# LEDS1.net
KiCad netlist of a schematic drawn in Altium Designer
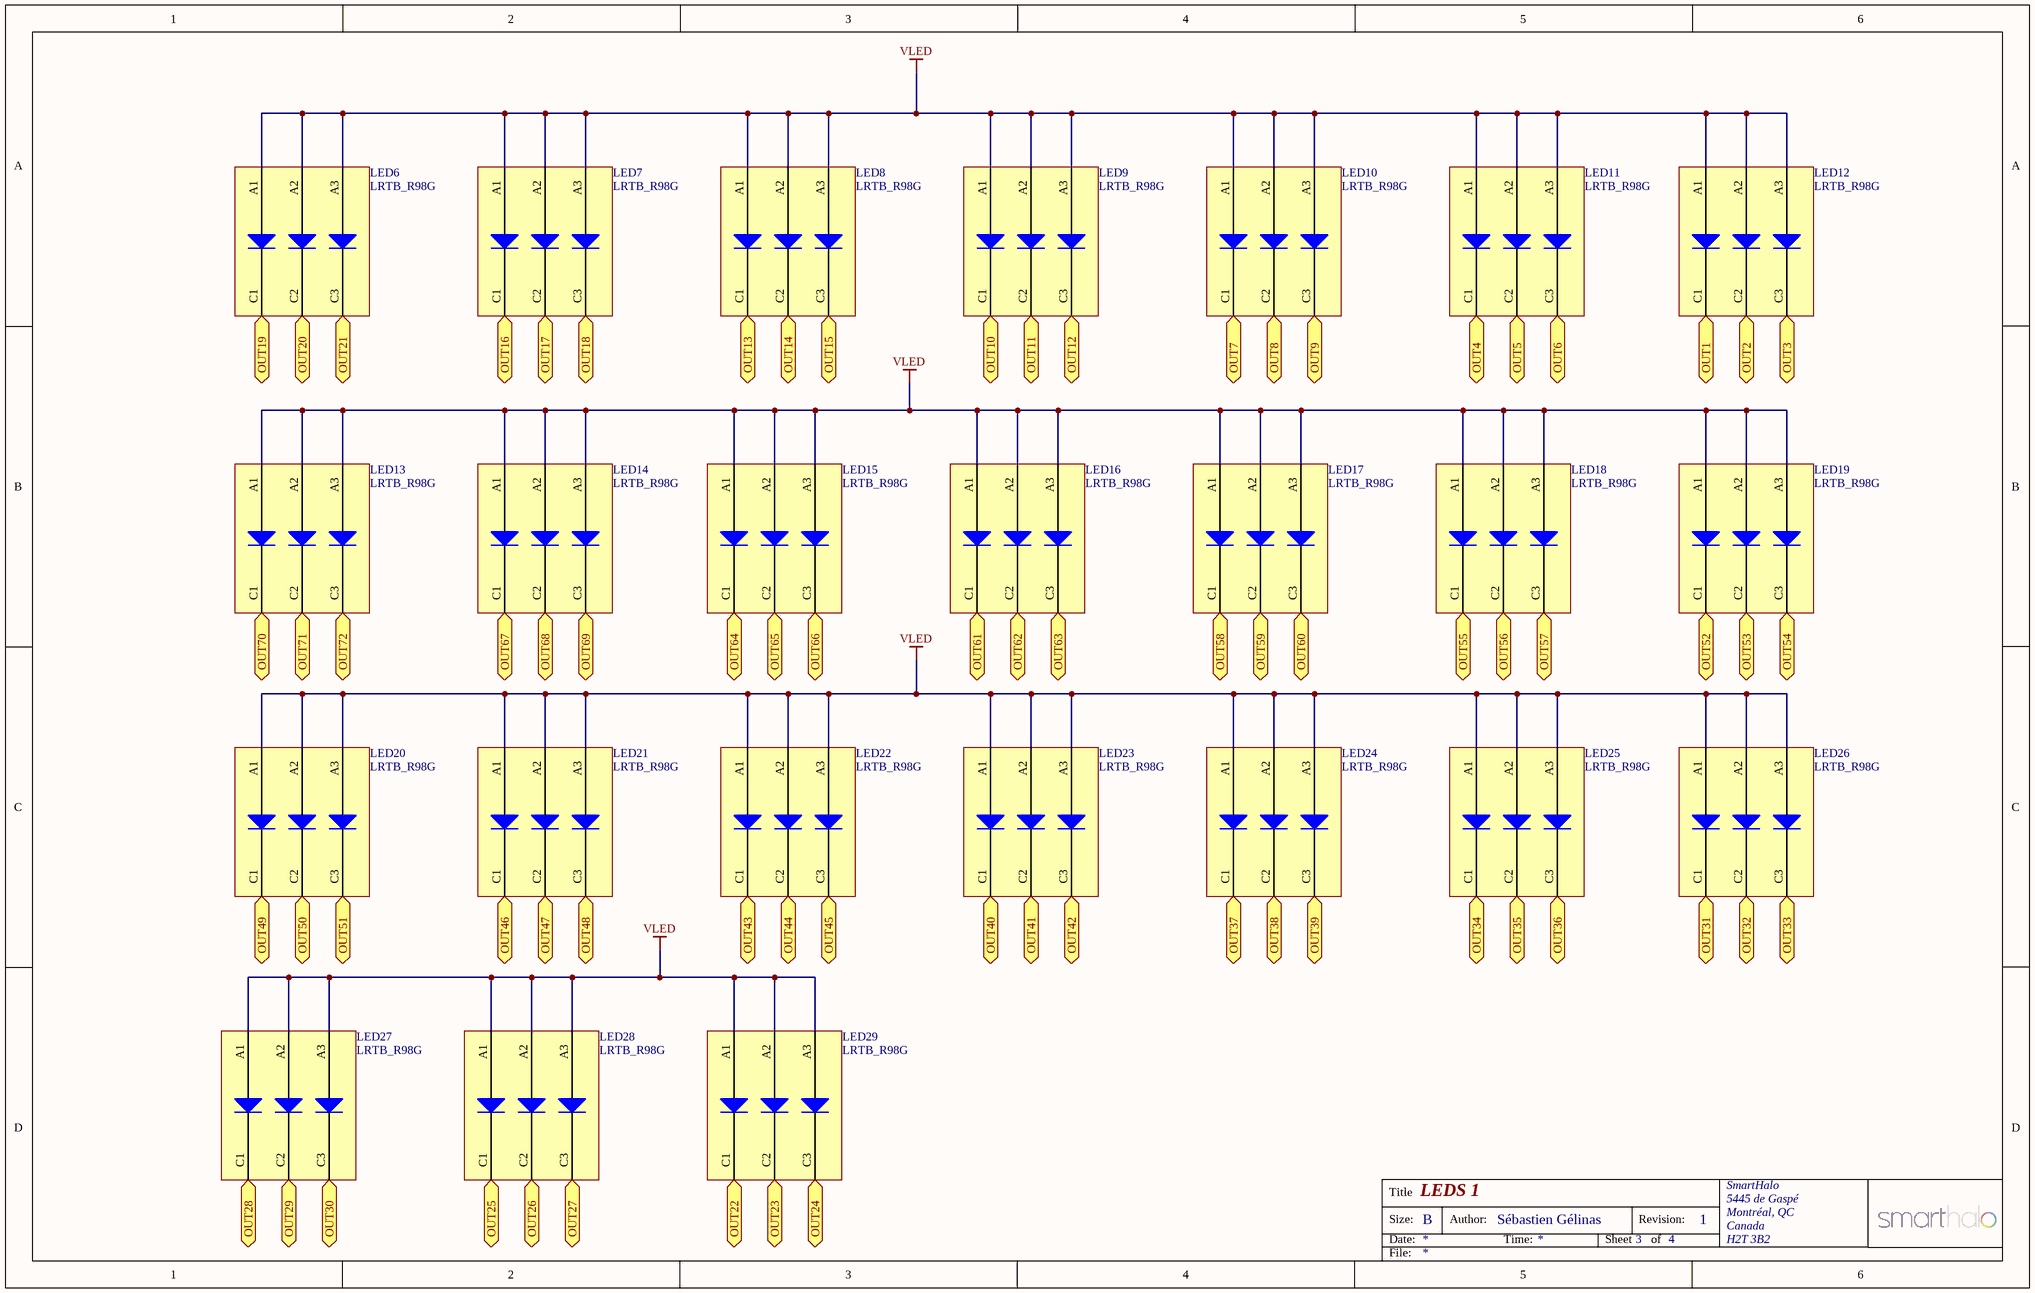
[diagram p0: LEDS1.SchDoc]

(export (version "E")
  (design (tool "Eeschema 10.0.6"))
  (components
    (comp (ref "LED6")
      (value "LRTB_R98G")
      (footprint "LRTB_R98G")
      (description "IC RGB LED OSRAM")
      (fields (field (name "MANUFACTURER") "OSRAM"))
      (libsource (lib "SmartHalo_Symbols") (part "LRTB_R98G"))
    )
    (comp (ref "LED7")
      (value "LRTB_R98G")
      (footprint "LRTB_R98G")
      (description "IC RGB LED OSRAM")
      (fields (field (name "MANUFACTURER") "OSRAM"))
      (libsource (lib "SmartHalo_Symbols") (part "LRTB_R98G"))
    )
    (comp (ref "LED8")
      (value "LRTB_R98G")
      (footprint "LRTB_R98G")
      (description "IC RGB LED OSRAM")
      (fields (field (name "MANUFACTURER") "OSRAM"))
      (libsource (lib "SmartHalo_Symbols") (part "LRTB_R98G"))
    )
    (comp (ref "LED9")
      (value "LRTB_R98G")
      (footprint "LRTB_R98G")
      (description "IC RGB LED OSRAM")
      (fields (field (name "MANUFACTURER") "OSRAM"))
      (libsource (lib "SmartHalo_Symbols") (part "LRTB_R98G"))
    )
    (comp (ref "LED10")
      (value "LRTB_R98G")
      (footprint "LRTB_R98G")
      (description "IC RGB LED OSRAM")
      (fields (field (name "MANUFACTURER") "OSRAM"))
      (libsource (lib "SmartHalo_Symbols") (part "LRTB_R98G"))
    )
    (comp (ref "LED11")
      (value "LRTB_R98G")
      (footprint "LRTB_R98G")
      (description "IC RGB LED OSRAM")
      (fields (field (name "MANUFACTURER") "OSRAM"))
      (libsource (lib "SmartHalo_Symbols") (part "LRTB_R98G"))
    )
    (comp (ref "LED12")
      (value "LRTB_R98G")
      (footprint "LRTB_R98G")
      (description "IC RGB LED OSRAM")
      (fields (field (name "MANUFACTURER") "OSRAM"))
      (libsource (lib "SmartHalo_Symbols") (part "LRTB_R98G"))
    )
    (comp (ref "LED13")
      (value "LRTB_R98G")
      (footprint "LRTB_R98G")
      (description "IC RGB LED OSRAM")
      (fields (field (name "MANUFACTURER") "OSRAM"))
      (libsource (lib "SmartHalo_Symbols") (part "LRTB_R98G"))
    )
    (comp (ref "LED14")
      (value "LRTB_R98G")
      (footprint "LRTB_R98G")
      (description "IC RGB LED OSRAM")
      (fields (field (name "MANUFACTURER") "OSRAM"))
      (libsource (lib "SmartHalo_Symbols") (part "LRTB_R98G"))
    )
    (comp (ref "LED15")
      (value "LRTB_R98G")
      (footprint "LRTB_R98G")
      (description "IC RGB LED OSRAM")
      (fields (field (name "MANUFACTURER") "OSRAM"))
      (libsource (lib "SmartHalo_Symbols") (part "LRTB_R98G"))
    )
    (comp (ref "LED16")
      (value "LRTB_R98G")
      (footprint "LRTB_R98G")
      (description "IC RGB LED OSRAM")
      (fields (field (name "MANUFACTURER") "OSRAM"))
      (libsource (lib "SmartHalo_Symbols") (part "LRTB_R98G"))
    )
    (comp (ref "LED17")
      (value "LRTB_R98G")
      (footprint "LRTB_R98G")
      (description "IC RGB LED OSRAM")
      (fields (field (name "MANUFACTURER") "OSRAM"))
      (libsource (lib "SmartHalo_Symbols") (part "LRTB_R98G"))
    )
    (comp (ref "LED18")
      (value "LRTB_R98G")
      (footprint "LRTB_R98G")
      (description "IC RGB LED OSRAM")
      (fields (field (name "MANUFACTURER") "OSRAM"))
      (libsource (lib "SmartHalo_Symbols") (part "LRTB_R98G"))
    )
    (comp (ref "LED19")
      (value "LRTB_R98G")
      (footprint "LRTB_R98G")
      (description "IC RGB LED OSRAM")
      (fields (field (name "MANUFACTURER") "OSRAM"))
      (libsource (lib "SmartHalo_Symbols") (part "LRTB_R98G"))
    )
    (comp (ref "LED20")
      (value "LRTB_R98G")
      (footprint "LRTB_R98G")
      (description "IC RGB LED OSRAM")
      (fields (field (name "MANUFACTURER") "OSRAM"))
      (libsource (lib "SmartHalo_Symbols") (part "LRTB_R98G"))
    )
    (comp (ref "LED21")
      (value "LRTB_R98G")
      (footprint "LRTB_R98G")
      (description "IC RGB LED OSRAM")
      (fields (field (name "MANUFACTURER") "OSRAM"))
      (libsource (lib "SmartHalo_Symbols") (part "LRTB_R98G"))
    )
    (comp (ref "LED22")
      (value "LRTB_R98G")
      (footprint "LRTB_R98G")
      (description "IC RGB LED OSRAM")
      (fields (field (name "MANUFACTURER") "OSRAM"))
      (libsource (lib "SmartHalo_Symbols") (part "LRTB_R98G"))
    )
    (comp (ref "LED23")
      (value "LRTB_R98G")
      (footprint "LRTB_R98G")
      (description "IC RGB LED OSRAM")
      (fields (field (name "MANUFACTURER") "OSRAM"))
      (libsource (lib "SmartHalo_Symbols") (part "LRTB_R98G"))
    )
    (comp (ref "LED24")
      (value "LRTB_R98G")
      (footprint "LRTB_R98G")
      (description "IC RGB LED OSRAM")
      (fields (field (name "MANUFACTURER") "OSRAM"))
      (libsource (lib "SmartHalo_Symbols") (part "LRTB_R98G"))
    )
    (comp (ref "LED25")
      (value "LRTB_R98G")
      (footprint "LRTB_R98G")
      (description "IC RGB LED OSRAM")
      (fields (field (name "MANUFACTURER") "OSRAM"))
      (libsource (lib "SmartHalo_Symbols") (part "LRTB_R98G"))
    )
    (comp (ref "LED26")
      (value "LRTB_R98G")
      (footprint "LRTB_R98G")
      (description "IC RGB LED OSRAM")
      (fields (field (name "MANUFACTURER") "OSRAM"))
      (libsource (lib "SmartHalo_Symbols") (part "LRTB_R98G"))
    )
    (comp (ref "LED27")
      (value "LRTB_R98G")
      (footprint "LRTB_R98G")
      (description "IC RGB LED OSRAM")
      (fields (field (name "MANUFACTURER") "OSRAM"))
      (libsource (lib "SmartHalo_Symbols") (part "LRTB_R98G"))
    )
    (comp (ref "LED28")
      (value "LRTB_R98G")
      (footprint "LRTB_R98G")
      (description "IC RGB LED OSRAM")
      (fields (field (name "MANUFACTURER") "OSRAM"))
      (libsource (lib "SmartHalo_Symbols") (part "LRTB_R98G"))
    )
    (comp (ref "LED29")
      (value "LRTB_R98G")
      (footprint "LRTB_R98G")
      (description "IC RGB LED OSRAM")
      (fields (field (name "MANUFACTURER") "OSRAM"))
      (libsource (lib "SmartHalo_Symbols") (part "LRTB_R98G"))
    )
  )
  (nets
    (net (code "1") (name "/OUT1") (class "Default")
      (node (ref "LED12") (pin "C1") (pinfunction "Cathode_Blue_C1") (pintype "passive"))
    )
    (net (code "2") (name "/OUT2") (class "Default")
      (node (ref "LED12") (pin "C2") (pinfunction "Cathode_Green_C2") (pintype "passive"))
    )
    (net (code "3") (name "/OUT3") (class "Default")
      (node (ref "LED12") (pin "C3") (pinfunction "Cathode_Red_C3") (pintype "passive"))
    )
    (net (code "4") (name "/OUT4") (class "Default")
      (node (ref "LED11") (pin "C1") (pinfunction "Cathode_Blue_C1") (pintype "passive"))
    )
    (net (code "5") (name "/OUT5") (class "Default")
      (node (ref "LED11") (pin "C2") (pinfunction "Cathode_Green_C2") (pintype "passive"))
    )
    (net (code "6") (name "/OUT6") (class "Default")
      (node (ref "LED11") (pin "C3") (pinfunction "Cathode_Red_C3") (pintype "passive"))
    )
    (net (code "7") (name "/OUT7") (class "Default")
      (node (ref "LED10") (pin "C1") (pinfunction "Cathode_Blue_C1") (pintype "passive"))
    )
    (net (code "8") (name "/OUT8") (class "Default")
      (node (ref "LED10") (pin "C2") (pinfunction "Cathode_Green_C2") (pintype "passive"))
    )
    (net (code "9") (name "/OUT9") (class "Default")
      (node (ref "LED10") (pin "C3") (pinfunction "Cathode_Red_C3") (pintype "passive"))
    )
    (net (code "10") (name "/OUT10") (class "Default")
      (node (ref "LED9") (pin "C1") (pinfunction "Cathode_Blue_C1") (pintype "passive"))
    )
    (net (code "11") (name "/OUT11") (class "Default")
      (node (ref "LED9") (pin "C2") (pinfunction "Cathode_Green_C2") (pintype "passive"))
    )
    (net (code "12") (name "/OUT12") (class "Default")
      (node (ref "LED9") (pin "C3") (pinfunction "Cathode_Red_C3") (pintype "passive"))
    )
    (net (code "13") (name "/OUT13") (class "Default")
      (node (ref "LED8") (pin "C1") (pinfunction "Cathode_Blue_C1") (pintype "passive"))
    )
    (net (code "14") (name "/OUT14") (class "Default")
      (node (ref "LED8") (pin "C2") (pinfunction "Cathode_Green_C2") (pintype "passive"))
    )
    (net (code "15") (name "/OUT15") (class "Default")
      (node (ref "LED8") (pin "C3") (pinfunction "Cathode_Red_C3") (pintype "passive"))
    )
    (net (code "16") (name "/OUT16") (class "Default")
      (node (ref "LED7") (pin "C1") (pinfunction "Cathode_Blue_C1") (pintype "passive"))
    )
    (net (code "17") (name "/OUT17") (class "Default")
      (node (ref "LED7") (pin "C2") (pinfunction "Cathode_Green_C2") (pintype "passive"))
    )
    (net (code "18") (name "/OUT18") (class "Default")
      (node (ref "LED7") (pin "C3") (pinfunction "Cathode_Red_C3") (pintype "passive"))
    )
    (net (code "19") (name "/OUT19") (class "Default")
      (node (ref "LED6") (pin "C1") (pinfunction "Cathode_Blue_C1") (pintype "passive"))
    )
    (net (code "20") (name "/OUT20") (class "Default")
      (node (ref "LED6") (pin "C2") (pinfunction "Cathode_Green_C2") (pintype "passive"))
    )
    (net (code "21") (name "/OUT21") (class "Default")
      (node (ref "LED6") (pin "C3") (pinfunction "Cathode_Red_C3") (pintype "passive"))
    )
    (net (code "22") (name "/OUT22") (class "Default")
      (node (ref "LED29") (pin "C1") (pinfunction "Cathode_Blue_C1") (pintype "passive"))
    )
    (net (code "23") (name "/OUT23") (class "Default")
      (node (ref "LED29") (pin "C2") (pinfunction "Cathode_Green_C2") (pintype "passive"))
    )
    (net (code "24") (name "/OUT24") (class "Default")
      (node (ref "LED29") (pin "C3") (pinfunction "Cathode_Red_C3") (pintype "passive"))
    )
    (net (code "25") (name "/OUT25") (class "Default")
      (node (ref "LED28") (pin "C1") (pinfunction "Cathode_Blue_C1") (pintype "passive"))
    )
    (net (code "26") (name "/OUT26") (class "Default")
      (node (ref "LED28") (pin "C2") (pinfunction "Cathode_Green_C2") (pintype "passive"))
    )
    (net (code "27") (name "/OUT27") (class "Default")
      (node (ref "LED28") (pin "C3") (pinfunction "Cathode_Red_C3") (pintype "passive"))
    )
    (net (code "28") (name "/OUT28") (class "Default")
      (node (ref "LED27") (pin "C1") (pinfunction "Cathode_Blue_C1") (pintype "passive"))
    )
    (net (code "29") (name "/OUT29") (class "Default")
      (node (ref "LED27") (pin "C2") (pinfunction "Cathode_Green_C2") (pintype "passive"))
    )
    (net (code "30") (name "/OUT30") (class "Default")
      (node (ref "LED27") (pin "C3") (pinfunction "Cathode_Red_C3") (pintype "passive"))
    )
    (net (code "31") (name "/OUT31") (class "Default")
      (node (ref "LED26") (pin "C1") (pinfunction "Cathode_Blue_C1") (pintype "passive"))
    )
    (net (code "32") (name "/OUT32") (class "Default")
      (node (ref "LED26") (pin "C2") (pinfunction "Cathode_Green_C2") (pintype "passive"))
    )
    (net (code "33") (name "/OUT33") (class "Default")
      (node (ref "LED26") (pin "C3") (pinfunction "Cathode_Red_C3") (pintype "passive"))
    )
    (net (code "34") (name "/OUT34") (class "Default")
      (node (ref "LED25") (pin "C1") (pinfunction "Cathode_Blue_C1") (pintype "passive"))
    )
    (net (code "35") (name "/OUT35") (class "Default")
      (node (ref "LED25") (pin "C2") (pinfunction "Cathode_Green_C2") (pintype "passive"))
    )
    (net (code "36") (name "/OUT36") (class "Default")
      (node (ref "LED25") (pin "C3") (pinfunction "Cathode_Red_C3") (pintype "passive"))
    )
    (net (code "37") (name "/OUT37") (class "Default")
      (node (ref "LED24") (pin "C1") (pinfunction "Cathode_Blue_C1") (pintype "passive"))
    )
    (net (code "38") (name "/OUT38") (class "Default")
      (node (ref "LED24") (pin "C2") (pinfunction "Cathode_Green_C2") (pintype "passive"))
    )
    (net (code "39") (name "/OUT39") (class "Default")
      (node (ref "LED24") (pin "C3") (pinfunction "Cathode_Red_C3") (pintype "passive"))
    )
    (net (code "40") (name "/OUT40") (class "Default")
      (node (ref "LED23") (pin "C1") (pinfunction "Cathode_Blue_C1") (pintype "passive"))
    )
    (net (code "41") (name "/OUT41") (class "Default")
      (node (ref "LED23") (pin "C2") (pinfunction "Cathode_Green_C2") (pintype "passive"))
    )
    (net (code "42") (name "/OUT42") (class "Default")
      (node (ref "LED23") (pin "C3") (pinfunction "Cathode_Red_C3") (pintype "passive"))
    )
    (net (code "43") (name "/OUT43") (class "Default")
      (node (ref "LED22") (pin "C1") (pinfunction "Cathode_Blue_C1") (pintype "passive"))
    )
    (net (code "44") (name "/OUT44") (class "Default")
      (node (ref "LED22") (pin "C2") (pinfunction "Cathode_Green_C2") (pintype "passive"))
    )
    (net (code "45") (name "/OUT45") (class "Default")
      (node (ref "LED22") (pin "C3") (pinfunction "Cathode_Red_C3") (pintype "passive"))
    )
    (net (code "46") (name "/OUT46") (class "Default")
      (node (ref "LED21") (pin "C1") (pinfunction "Cathode_Blue_C1") (pintype "passive"))
    )
    (net (code "47") (name "/OUT47") (class "Default")
      (node (ref "LED21") (pin "C2") (pinfunction "Cathode_Green_C2") (pintype "passive"))
    )
    (net (code "48") (name "/OUT48") (class "Default")
      (node (ref "LED21") (pin "C3") (pinfunction "Cathode_Red_C3") (pintype "passive"))
    )
    (net (code "49") (name "/OUT49") (class "Default")
      (node (ref "LED20") (pin "C1") (pinfunction "Cathode_Blue_C1") (pintype "passive"))
    )
    (net (code "50") (name "/OUT50") (class "Default")
      (node (ref "LED20") (pin "C2") (pinfunction "Cathode_Green_C2") (pintype "passive"))
    )
    (net (code "51") (name "/OUT51") (class "Default")
      (node (ref "LED20") (pin "C3") (pinfunction "Cathode_Red_C3") (pintype "passive"))
    )
    (net (code "52") (name "/OUT52") (class "Default")
      (node (ref "LED19") (pin "C1") (pinfunction "Cathode_Blue_C1") (pintype "passive"))
    )
    (net (code "53") (name "/OUT53") (class "Default")
      (node (ref "LED19") (pin "C2") (pinfunction "Cathode_Green_C2") (pintype "passive"))
    )
    (net (code "54") (name "/OUT54") (class "Default")
      (node (ref "LED19") (pin "C3") (pinfunction "Cathode_Red_C3") (pintype "passive"))
    )
    (net (code "55") (name "/OUT55") (class "Default")
      (node (ref "LED18") (pin "C1") (pinfunction "Cathode_Blue_C1") (pintype "passive"))
    )
    (net (code "56") (name "/OUT56") (class "Default")
      (node (ref "LED18") (pin "C2") (pinfunction "Cathode_Green_C2") (pintype "passive"))
    )
    (net (code "57") (name "/OUT57") (class "Default")
      (node (ref "LED18") (pin "C3") (pinfunction "Cathode_Red_C3") (pintype "passive"))
    )
    (net (code "58") (name "/OUT58") (class "Default")
      (node (ref "LED17") (pin "C1") (pinfunction "Cathode_Blue_C1") (pintype "passive"))
    )
    (net (code "59") (name "/OUT59") (class "Default")
      (node (ref "LED17") (pin "C2") (pinfunction "Cathode_Green_C2") (pintype "passive"))
    )
    (net (code "60") (name "/OUT60") (class "Default")
      (node (ref "LED17") (pin "C3") (pinfunction "Cathode_Red_C3") (pintype "passive"))
    )
    (net (code "61") (name "/OUT61") (class "Default")
      (node (ref "LED16") (pin "C1") (pinfunction "Cathode_Blue_C1") (pintype "passive"))
    )
    (net (code "62") (name "/OUT62") (class "Default")
      (node (ref "LED16") (pin "C2") (pinfunction "Cathode_Green_C2") (pintype "passive"))
    )
    (net (code "63") (name "/OUT63") (class "Default")
      (node (ref "LED16") (pin "C3") (pinfunction "Cathode_Red_C3") (pintype "passive"))
    )
    (net (code "64") (name "/OUT64") (class "Default")
      (node (ref "LED15") (pin "C1") (pinfunction "Cathode_Blue_C1") (pintype "passive"))
    )
    (net (code "65") (name "/OUT65") (class "Default")
      (node (ref "LED15") (pin "C2") (pinfunction "Cathode_Green_C2") (pintype "passive"))
    )
    (net (code "66") (name "/OUT66") (class "Default")
      (node (ref "LED15") (pin "C3") (pinfunction "Cathode_Red_C3") (pintype "passive"))
    )
    (net (code "67") (name "/OUT67") (class "Default")
      (node (ref "LED14") (pin "C1") (pinfunction "Cathode_Blue_C1") (pintype "passive"))
    )
    (net (code "68") (name "/OUT68") (class "Default")
      (node (ref "LED14") (pin "C2") (pinfunction "Cathode_Green_C2") (pintype "passive"))
    )
    (net (code "69") (name "/OUT69") (class "Default")
      (node (ref "LED14") (pin "C3") (pinfunction "Cathode_Red_C3") (pintype "passive"))
    )
    (net (code "70") (name "/OUT70") (class "Default")
      (node (ref "LED13") (pin "C1") (pinfunction "Cathode_Blue_C1") (pintype "passive"))
    )
    (net (code "71") (name "/OUT71") (class "Default")
      (node (ref "LED13") (pin "C2") (pinfunction "Cathode_Green_C2") (pintype "passive"))
    )
    (net (code "72") (name "/OUT72") (class "Default")
      (node (ref "LED13") (pin "C3") (pinfunction "Cathode_Red_C3") (pintype "passive"))
    )
    (net (code "73") (name "VLED") (class "Default")
      (node (ref "LED10") (pin "A1") (pinfunction "Anode_Blue_A1") (pintype "passive"))
      (node (ref "LED10") (pin "A2") (pinfunction "Anode_Green_A2") (pintype "passive"))
      (node (ref "LED10") (pin "A3") (pinfunction "Anode_Red_A3") (pintype "passive"))
      (node (ref "LED11") (pin "A1") (pinfunction "Anode_Blue_A1") (pintype "passive"))
      (node (ref "LED11") (pin "A2") (pinfunction "Anode_Green_A2") (pintype "passive"))
      (node (ref "LED11") (pin "A3") (pinfunction "Anode_Red_A3") (pintype "passive"))
      (node (ref "LED12") (pin "A1") (pinfunction "Anode_Blue_A1") (pintype "passive"))
      (node (ref "LED12") (pin "A2") (pinfunction "Anode_Green_A2") (pintype "passive"))
      (node (ref "LED12") (pin "A3") (pinfunction "Anode_Red_A3") (pintype "passive"))
      (node (ref "LED13") (pin "A1") (pinfunction "Anode_Blue_A1") (pintype "passive"))
      (node (ref "LED13") (pin "A2") (pinfunction "Anode_Green_A2") (pintype "passive"))
      (node (ref "LED13") (pin "A3") (pinfunction "Anode_Red_A3") (pintype "passive"))
      (node (ref "LED14") (pin "A1") (pinfunction "Anode_Blue_A1") (pintype "passive"))
      (node (ref "LED14") (pin "A2") (pinfunction "Anode_Green_A2") (pintype "passive"))
      (node (ref "LED14") (pin "A3") (pinfunction "Anode_Red_A3") (pintype "passive"))
      (node (ref "LED15") (pin "A1") (pinfunction "Anode_Blue_A1") (pintype "passive"))
      (node (ref "LED15") (pin "A2") (pinfunction "Anode_Green_A2") (pintype "passive"))
      (node (ref "LED15") (pin "A3") (pinfunction "Anode_Red_A3") (pintype "passive"))
      (node (ref "LED16") (pin "A1") (pinfunction "Anode_Blue_A1") (pintype "passive"))
      (node (ref "LED16") (pin "A2") (pinfunction "Anode_Green_A2") (pintype "passive"))
      (node (ref "LED16") (pin "A3") (pinfunction "Anode_Red_A3") (pintype "passive"))
      (node (ref "LED17") (pin "A1") (pinfunction "Anode_Blue_A1") (pintype "passive"))
      (node (ref "LED17") (pin "A2") (pinfunction "Anode_Green_A2") (pintype "passive"))
      (node (ref "LED17") (pin "A3") (pinfunction "Anode_Red_A3") (pintype "passive"))
      (node (ref "LED18") (pin "A1") (pinfunction "Anode_Blue_A1") (pintype "passive"))
      (node (ref "LED18") (pin "A2") (pinfunction "Anode_Green_A2") (pintype "passive"))
      (node (ref "LED18") (pin "A3") (pinfunction "Anode_Red_A3") (pintype "passive"))
      (node (ref "LED19") (pin "A1") (pinfunction "Anode_Blue_A1") (pintype "passive"))
      (node (ref "LED19") (pin "A2") (pinfunction "Anode_Green_A2") (pintype "passive"))
      (node (ref "LED19") (pin "A3") (pinfunction "Anode_Red_A3") (pintype "passive"))
      (node (ref "LED20") (pin "A1") (pinfunction "Anode_Blue_A1") (pintype "passive"))
      (node (ref "LED20") (pin "A2") (pinfunction "Anode_Green_A2") (pintype "passive"))
      (node (ref "LED20") (pin "A3") (pinfunction "Anode_Red_A3") (pintype "passive"))
      (node (ref "LED21") (pin "A1") (pinfunction "Anode_Blue_A1") (pintype "passive"))
      (node (ref "LED21") (pin "A2") (pinfunction "Anode_Green_A2") (pintype "passive"))
      (node (ref "LED21") (pin "A3") (pinfunction "Anode_Red_A3") (pintype "passive"))
      (node (ref "LED22") (pin "A1") (pinfunction "Anode_Blue_A1") (pintype "passive"))
      (node (ref "LED22") (pin "A2") (pinfunction "Anode_Green_A2") (pintype "passive"))
      (node (ref "LED22") (pin "A3") (pinfunction "Anode_Red_A3") (pintype "passive"))
      (node (ref "LED23") (pin "A1") (pinfunction "Anode_Blue_A1") (pintype "passive"))
      (node (ref "LED23") (pin "A2") (pinfunction "Anode_Green_A2") (pintype "passive"))
      (node (ref "LED23") (pin "A3") (pinfunction "Anode_Red_A3") (pintype "passive"))
      (node (ref "LED24") (pin "A1") (pinfunction "Anode_Blue_A1") (pintype "passive"))
      (node (ref "LED24") (pin "A2") (pinfunction "Anode_Green_A2") (pintype "passive"))
      (node (ref "LED24") (pin "A3") (pinfunction "Anode_Red_A3") (pintype "passive"))
      (node (ref "LED25") (pin "A1") (pinfunction "Anode_Blue_A1") (pintype "passive"))
      (node (ref "LED25") (pin "A2") (pinfunction "Anode_Green_A2") (pintype "passive"))
      (node (ref "LED25") (pin "A3") (pinfunction "Anode_Red_A3") (pintype "passive"))
      (node (ref "LED26") (pin "A1") (pinfunction "Anode_Blue_A1") (pintype "passive"))
      (node (ref "LED26") (pin "A2") (pinfunction "Anode_Green_A2") (pintype "passive"))
      (node (ref "LED26") (pin "A3") (pinfunction "Anode_Red_A3") (pintype "passive"))
      (node (ref "LED27") (pin "A1") (pinfunction "Anode_Blue_A1") (pintype "passive"))
      (node (ref "LED27") (pin "A2") (pinfunction "Anode_Green_A2") (pintype "passive"))
      (node (ref "LED27") (pin "A3") (pinfunction "Anode_Red_A3") (pintype "passive"))
      (node (ref "LED28") (pin "A1") (pinfunction "Anode_Blue_A1") (pintype "passive"))
      (node (ref "LED28") (pin "A2") (pinfunction "Anode_Green_A2") (pintype "passive"))
      (node (ref "LED28") (pin "A3") (pinfunction "Anode_Red_A3") (pintype "passive"))
      (node (ref "LED29") (pin "A1") (pinfunction "Anode_Blue_A1") (pintype "passive"))
      (node (ref "LED29") (pin "A2") (pinfunction "Anode_Green_A2") (pintype "passive"))
      (node (ref "LED29") (pin "A3") (pinfunction "Anode_Red_A3") (pintype "passive"))
      (node (ref "LED6") (pin "A1") (pinfunction "Anode_Blue_A1") (pintype "passive"))
      (node (ref "LED6") (pin "A2") (pinfunction "Anode_Green_A2") (pintype "passive"))
      (node (ref "LED6") (pin "A3") (pinfunction "Anode_Red_A3") (pintype "passive"))
      (node (ref "LED7") (pin "A1") (pinfunction "Anode_Blue_A1") (pintype "passive"))
      (node (ref "LED7") (pin "A2") (pinfunction "Anode_Green_A2") (pintype "passive"))
      (node (ref "LED7") (pin "A3") (pinfunction "Anode_Red_A3") (pintype "passive"))
      (node (ref "LED8") (pin "A1") (pinfunction "Anode_Blue_A1") (pintype "passive"))
      (node (ref "LED8") (pin "A2") (pinfunction "Anode_Green_A2") (pintype "passive"))
      (node (ref "LED8") (pin "A3") (pinfunction "Anode_Red_A3") (pintype "passive"))
      (node (ref "LED9") (pin "A1") (pinfunction "Anode_Blue_A1") (pintype "passive"))
      (node (ref "LED9") (pin "A2") (pinfunction "Anode_Green_A2") (pintype "passive"))
      (node (ref "LED9") (pin "A3") (pinfunction "Anode_Red_A3") (pintype "passive"))
    )
  )
)
